# 1P3W_v1p3.net
KiCad netlist of a schematic drawn in EAGLE
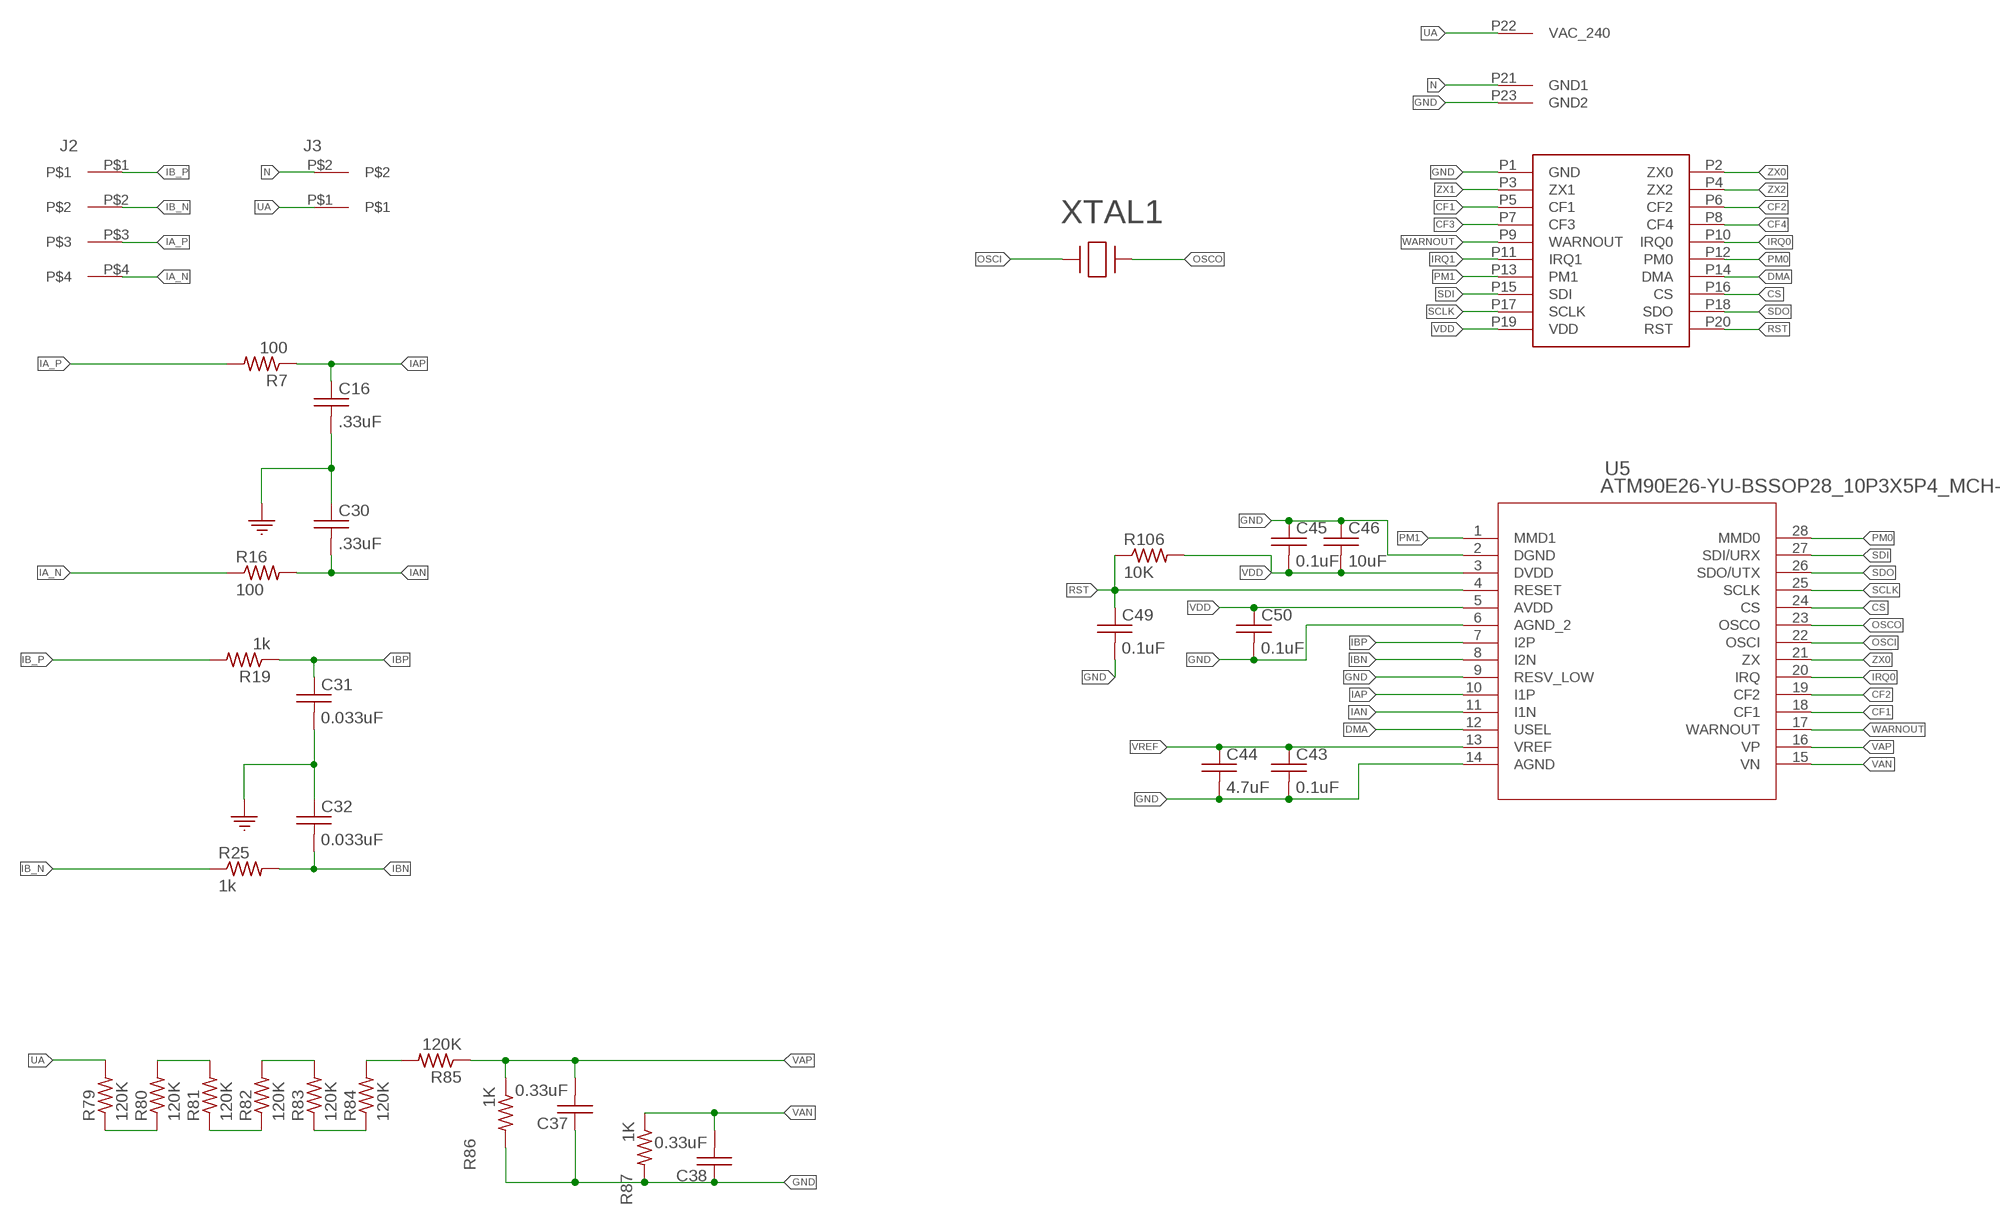
[diagram p0: schematic, sheet 1]

(export (version "E")
  (design (tool "Eeschema 10.0.6"))
  (components
    (comp (ref "C16")
      (value ".33uF")
      (footprint "eagle-import:0402")
      (libsource (lib "eagle-import") (part "C_0402"))
    )
    (comp (ref "C30")
      (value ".33uF")
      (footprint "eagle-import:0402")
      (libsource (lib "eagle-import") (part "C_0402"))
    )
    (comp (ref "C31")
      (value "0.033uF")
      (footprint "eagle-import:0402")
      (libsource (lib "eagle-import") (part "C_0402"))
    )
    (comp (ref "C32")
      (value "0.033uF")
      (footprint "eagle-import:0402")
      (libsource (lib "eagle-import") (part "C_0402"))
    )
    (comp (ref "C37")
      (value "0.33uF")
      (footprint "eagle-import:0402")
      (libsource (lib "eagle-import") (part "C_0402"))
    )
    (comp (ref "C38")
      (value "0.33uF")
      (footprint "eagle-import:0402")
      (libsource (lib "eagle-import") (part "C_0402"))
    )
    (comp (ref "C43")
      (value "0.1uF")
      (footprint "eagle-import:0402")
      (libsource (lib "eagle-import") (part "C_0402"))
    )
    (comp (ref "C44")
      (value "4.7uF")
      (footprint "eagle-import:0402")
      (libsource (lib "eagle-import") (part "C_0402"))
    )
    (comp (ref "C45")
      (value "0.1uF")
      (footprint "eagle-import:0402")
      (libsource (lib "eagle-import") (part "C_0402"))
    )
    (comp (ref "C46")
      (value "10uF")
      (footprint "eagle-import:0402")
      (libsource (lib "eagle-import") (part "C_0402"))
    )
    (comp (ref "C49")
      (value "0.1uF")
      (footprint "eagle-import:0402")
      (libsource (lib "eagle-import") (part "C_0402"))
    )
    (comp (ref "C50")
      (value "0.1uF")
      (footprint "eagle-import:0402")
      (libsource (lib "eagle-import") (part "C_0402"))
    )
    (comp (ref "J2")
      (value "3.81MM_1_X_4_RT_ANGLE_PLUG_HEADER")
      (footprint "eagle-import:1X4_3.81MM_PITCH")
      (libsource (lib "eagle-import") (part "3.81MM_1_X_4_RT_ANGLE_PLUG_HEADER"))
    )
    (comp (ref "J3")
      (value "3.81MM_1_X_2_RT_ANGLE_PLUG_HEADER")
      (footprint "eagle-import:2_3.81MM_PITCH")
      (libsource (lib "eagle-import") (part "3.81MM_1_X_2_RT_ANGLE_PLUG_HEADER"))
    )
    (comp (ref "R7")
      (value "100")
      (footprint "eagle-import:0402")
      (libsource (lib "eagle-import") (part "R_0402"))
    )
    (comp (ref "R16")
      (value "100")
      (footprint "eagle-import:0402")
      (libsource (lib "eagle-import") (part "R_0402"))
    )
    (comp (ref "R19")
      (value "1k")
      (footprint "eagle-import:0402")
      (libsource (lib "eagle-import") (part "R_0402"))
    )
    (comp (ref "R25")
      (value "1k")
      (footprint "eagle-import:0402")
      (libsource (lib "eagle-import") (part "R_0402"))
    )
    (comp (ref "R79")
      (value "120K")
      (footprint "eagle-import:0402")
      (libsource (lib "eagle-import") (part "R_0402"))
    )
    (comp (ref "R80")
      (value "120K")
      (footprint "eagle-import:0402")
      (libsource (lib "eagle-import") (part "R_0402"))
    )
    (comp (ref "R81")
      (value "120K")
      (footprint "eagle-import:0402")
      (libsource (lib "eagle-import") (part "R_0402"))
    )
    (comp (ref "R82")
      (value "120K")
      (footprint "eagle-import:0402")
      (libsource (lib "eagle-import") (part "R_0402"))
    )
    (comp (ref "R83")
      (value "120K")
      (footprint "eagle-import:0402")
      (libsource (lib "eagle-import") (part "R_0402"))
    )
    (comp (ref "R84")
      (value "120K")
      (footprint "eagle-import:0402")
      (libsource (lib "eagle-import") (part "R_0402"))
    )
    (comp (ref "R85")
      (value "120K")
      (footprint "eagle-import:0402")
      (libsource (lib "eagle-import") (part "R_0402"))
    )
    (comp (ref "R86")
      (value "1K")
      (footprint "eagle-import:0402")
      (libsource (lib "eagle-import") (part "R_0402"))
    )
    (comp (ref "R87")
      (value "1K")
      (footprint "eagle-import:0402")
      (libsource (lib "eagle-import") (part "R_0402"))
    )
    (comp (ref "R106")
      (value "10K")
      (footprint "eagle-import:0402")
      (libsource (lib "eagle-import") (part "R_0402"))
    )
    (comp (ref "U$1")
      (value "METER_BASE")
      (footprint "eagle-import:METER_BASE")
      (libsource (lib "eagle-import") (part "METER_BASE"))
    )
    (comp (ref "U5")
      (value "ATM90E26-YU-BSSOP28_10P3X5P4_MCH-M")
      (footprint "eagle-import:SSOP28_10P3X5P4_MCH-M")
      (fields
        (field (name "MANUFACTURER_PART_NUMBER") "ATM90E26-YU-B")
        (field (name "COPYRIGHT") "Copyright (C) 2018 Accelerated Designs. All rights reserved")
      )
      (libsource (lib "eagle-import") (part "ATM90E26-YU-BSSOP28_10P3X5P4_MCH-M"))
    )
    (comp (ref "XTAL1")
      (value "ABLS-8.192MHZ-B2-TXTAL_HC/49US_ABLS_ABR-M")
      (footprint "eagle-import:XTAL_HC_49US_ABLS_ABR-M")
      (fields
        (field (name "MANUFACTURER_PART_NUMBER") "ABLS-8.192MHZ-B2-T")
        (field (name "COPYRIGHT") "Copyright (C) 2018 Accelerated Designs. All rights reserved")
      )
      (libsource (lib "eagle-import") (part "ABLS-8.192MHZ-B2-TXTAL_HC/49US_ABLS_ABR-M"))
    )
  )
  (nets
    (net (code "1") (name "CF1") (class "Default")
      (node (ref "U$1") (pin "P5") (pinfunction "CF1_P5") (pintype "bidirectional"))
      (node (ref "U5") (pin "18") (pinfunction "CF1_18") (pintype "bidirectional"))
    )
    (net (code "2") (name "CF2") (class "Default")
      (node (ref "U$1") (pin "P6") (pinfunction "CF2_P6") (pintype "bidirectional"))
      (node (ref "U5") (pin "19") (pinfunction "CF2_19") (pintype "bidirectional"))
    )
    (net (code "3") (name "CF3") (class "Default")
      (node (ref "U$1") (pin "P7") (pinfunction "CF3_P7") (pintype "bidirectional"))
    )
    (net (code "4") (name "CF4") (class "Default")
      (node (ref "U$1") (pin "P8") (pinfunction "CF4_P8") (pintype "bidirectional"))
    )
    (net (code "5") (name "CS") (class "Default")
      (node (ref "U$1") (pin "P16") (pinfunction "CS_P16") (pintype "bidirectional"))
      (node (ref "U5") (pin "24") (pinfunction "CS_24") (pintype "passive"))
    )
    (net (code "6") (name "DMA") (class "Default")
      (node (ref "U$1") (pin "P14") (pinfunction "DMA_P14") (pintype "bidirectional"))
      (node (ref "U5") (pin "12") (pinfunction "USEL_12") (pintype "passive"))
    )
    (net (code "7") (name "GND") (class "Default")
      (node (ref "C16") (pin "P$2") (pinfunction "2_P$2") (pintype "passive"))
      (node (ref "C30") (pin "P$1") (pinfunction "1_P$1") (pintype "passive"))
      (node (ref "C31") (pin "P$2") (pinfunction "2_P$2") (pintype "passive"))
      (node (ref "C32") (pin "P$1") (pinfunction "1_P$1") (pintype "passive"))
      (node (ref "C37") (pin "P$1") (pinfunction "1_P$1") (pintype "passive"))
      (node (ref "C38") (pin "P$1") (pinfunction "1_P$1") (pintype "passive"))
      (node (ref "C43") (pin "P$2") (pinfunction "2_P$2") (pintype "passive"))
      (node (ref "C44") (pin "P$2") (pinfunction "2_P$2") (pintype "passive"))
      (node (ref "C45") (pin "P$1") (pinfunction "1_P$1") (pintype "passive"))
      (node (ref "C46") (pin "P$1") (pinfunction "1_P$1") (pintype "passive"))
      (node (ref "C49") (pin "P$2") (pinfunction "2_P$2") (pintype "passive"))
      (node (ref "C50") (pin "P$2") (pinfunction "2_P$2") (pintype "passive"))
      (node (ref "R86") (pin "P$2") (pinfunction "2_P$2") (pintype "passive"))
      (node (ref "R87") (pin "P$2") (pinfunction "2_P$2") (pintype "passive"))
      (node (ref "U$1") (pin "P1") (pinfunction "GND_P1") (pintype "bidirectional"))
      (node (ref "U$1") (pin "P23") (pinfunction "GND2_P23") (pintype "bidirectional"))
      (node (ref "U5") (pin "14") (pinfunction "AGND_14") (pintype "passive"))
      (node (ref "U5") (pin "2") (pinfunction "DGND_2") (pintype "passive"))
      (node (ref "U5") (pin "6") (pinfunction "AGND_2_6") (pintype "passive"))
      (node (ref "U5") (pin "9") (pinfunction "RESV_LOW_9") (pintype "passive"))
    )
    (net (code "8") (name "IAN") (class "Default")
      (node (ref "C30") (pin "P$2") (pinfunction "2_P$2") (pintype "passive"))
      (node (ref "R16") (pin "P$2") (pinfunction "2_P$2") (pintype "passive"))
      (node (ref "U5") (pin "11") (pinfunction "I1N_11") (pintype "bidirectional"))
    )
    (net (code "9") (name "IAP") (class "Default")
      (node (ref "C16") (pin "P$1") (pinfunction "1_P$1") (pintype "passive"))
      (node (ref "R7") (pin "P$1") (pinfunction "1_P$1") (pintype "passive"))
      (node (ref "U5") (pin "10") (pinfunction "I1P_10") (pintype "bidirectional"))
    )
    (net (code "10") (name "IA_N") (class "Default")
      (node (ref "J2") (pin "P$4") (pinfunction "P$4_P$4") (pintype "bidirectional"))
      (node (ref "R16") (pin "P$1") (pinfunction "1_P$1") (pintype "passive"))
    )
    (net (code "11") (name "IA_P") (class "Default")
      (node (ref "J2") (pin "P$3") (pinfunction "P$3_P$3") (pintype "bidirectional"))
      (node (ref "R7") (pin "P$2") (pinfunction "2_P$2") (pintype "passive"))
    )
    (net (code "12") (name "IBN") (class "Default")
      (node (ref "C32") (pin "P$2") (pinfunction "2_P$2") (pintype "passive"))
      (node (ref "R25") (pin "P$2") (pinfunction "2_P$2") (pintype "passive"))
      (node (ref "U5") (pin "8") (pinfunction "I2N_8") (pintype "bidirectional"))
    )
    (net (code "13") (name "IBP") (class "Default")
      (node (ref "C31") (pin "P$1") (pinfunction "1_P$1") (pintype "passive"))
      (node (ref "R19") (pin "P$1") (pinfunction "1_P$1") (pintype "passive"))
      (node (ref "U5") (pin "7") (pinfunction "I2P_7") (pintype "bidirectional"))
    )
    (net (code "14") (name "IB_N") (class "Default")
      (node (ref "J2") (pin "P$2") (pinfunction "P$2_P$2") (pintype "bidirectional"))
      (node (ref "R25") (pin "P$1") (pinfunction "1_P$1") (pintype "passive"))
    )
    (net (code "15") (name "IB_P") (class "Default")
      (node (ref "J2") (pin "P$1") (pinfunction "P$1_P$1") (pintype "bidirectional"))
      (node (ref "R19") (pin "P$2") (pinfunction "2_P$2") (pintype "passive"))
    )
    (net (code "16") (name "IRQ0") (class "Default")
      (node (ref "U$1") (pin "P10") (pinfunction "IRQ0_P10") (pintype "bidirectional"))
      (node (ref "U5") (pin "20") (pinfunction "IRQ_20") (pintype "passive"))
    )
    (net (code "17") (name "IRQ1") (class "Default")
      (node (ref "U$1") (pin "P11") (pinfunction "IRQ1_P11") (pintype "bidirectional"))
    )
    (net (code "18") (name "N") (class "Default")
      (node (ref "J3") (pin "P$2") (pinfunction "P$2_P$2") (pintype "bidirectional"))
      (node (ref "U$1") (pin "P21") (pinfunction "GND1_P21") (pintype "bidirectional"))
    )
    (net (code "19") (name "Net-(R79-1)") (class "Default")
      (node (ref "R79") (pin "P$1") (pinfunction "1_P$1") (pintype "passive"))
      (node (ref "R80") (pin "P$1") (pinfunction "1_P$1") (pintype "passive"))
    )
    (net (code "20") (name "Net-(R80-2)") (class "Default")
      (node (ref "R80") (pin "P$2") (pinfunction "2_P$2") (pintype "passive"))
      (node (ref "R81") (pin "P$2") (pinfunction "2_P$2") (pintype "passive"))
    )
    (net (code "21") (name "Net-(R81-1)") (class "Default")
      (node (ref "R81") (pin "P$1") (pinfunction "1_P$1") (pintype "passive"))
      (node (ref "R82") (pin "P$1") (pinfunction "1_P$1") (pintype "passive"))
    )
    (net (code "22") (name "Net-(R82-2)") (class "Default")
      (node (ref "R82") (pin "P$2") (pinfunction "2_P$2") (pintype "passive"))
      (node (ref "R83") (pin "P$2") (pinfunction "2_P$2") (pintype "passive"))
    )
    (net (code "23") (name "Net-(R83-1)") (class "Default")
      (node (ref "R83") (pin "P$1") (pinfunction "1_P$1") (pintype "passive"))
      (node (ref "R84") (pin "P$1") (pinfunction "1_P$1") (pintype "passive"))
    )
    (net (code "24") (name "Net-(R84-2)") (class "Default")
      (node (ref "R84") (pin "P$2") (pinfunction "2_P$2") (pintype "passive"))
      (node (ref "R85") (pin "P$2") (pinfunction "2_P$2") (pintype "passive"))
    )
    (net (code "25") (name "OSCI") (class "Default")
      (node (ref "U5") (pin "22") (pinfunction "OSCI_22") (pintype "passive"))
      (node (ref "XTAL1") (pin "1") (pinfunction "1_1") (pintype "passive"))
    )
    (net (code "26") (name "OSCO") (class "Default")
      (node (ref "U5") (pin "23") (pinfunction "OSCO_23") (pintype "passive"))
      (node (ref "XTAL1") (pin "2") (pinfunction "2_2") (pintype "passive"))
    )
    (net (code "27") (name "PM0") (class "Default")
      (node (ref "U$1") (pin "P12") (pinfunction "PM0_P12") (pintype "bidirectional"))
      (node (ref "U5") (pin "28") (pinfunction "MMD0_28") (pintype "bidirectional"))
    )
    (net (code "28") (name "PM1") (class "Default")
      (node (ref "U$1") (pin "P13") (pinfunction "PM1_P13") (pintype "bidirectional"))
      (node (ref "U5") (pin "1") (pinfunction "MMD1_1") (pintype "bidirectional"))
    )
    (net (code "29") (name "RST") (class "Default")
      (node (ref "C49") (pin "P$1") (pinfunction "1_P$1") (pintype "passive"))
      (node (ref "R106") (pin "P$1") (pinfunction "1_P$1") (pintype "passive"))
      (node (ref "U$1") (pin "P20") (pinfunction "RST_P20") (pintype "bidirectional"))
      (node (ref "U5") (pin "4") (pinfunction "RESET_4") (pintype "passive"))
    )
    (net (code "30") (name "SCLK") (class "Default")
      (node (ref "U$1") (pin "P17") (pinfunction "SCLK_P17") (pintype "bidirectional"))
      (node (ref "U5") (pin "25") (pinfunction "SCLK_25") (pintype "passive"))
    )
    (net (code "31") (name "SDI") (class "Default")
      (node (ref "U$1") (pin "P15") (pinfunction "SDI_P15") (pintype "bidirectional"))
      (node (ref "U5") (pin "27") (pinfunction "SDI/URX_27") (pintype "passive"))
    )
    (net (code "32") (name "SDO") (class "Default")
      (node (ref "U$1") (pin "P18") (pinfunction "SDO_P18") (pintype "bidirectional"))
      (node (ref "U5") (pin "26") (pinfunction "SDO/UTX_26") (pintype "passive"))
    )
    (net (code "33") (name "UA") (class "Default")
      (node (ref "J3") (pin "P$1") (pinfunction "P$1_P$1") (pintype "bidirectional"))
      (node (ref "R79") (pin "P$2") (pinfunction "2_P$2") (pintype "passive"))
      (node (ref "U$1") (pin "P22") (pinfunction "VAC_240_P22") (pintype "bidirectional"))
    )
    (net (code "34") (name "VAN") (class "Default")
      (node (ref "C38") (pin "P$2") (pinfunction "2_P$2") (pintype "passive"))
      (node (ref "R87") (pin "P$1") (pinfunction "1_P$1") (pintype "passive"))
      (node (ref "U5") (pin "15") (pinfunction "VN_15") (pintype "passive"))
    )
    (net (code "35") (name "VAP") (class "Default")
      (node (ref "C37") (pin "P$2") (pinfunction "2_P$2") (pintype "passive"))
      (node (ref "R85") (pin "P$1") (pinfunction "1_P$1") (pintype "passive"))
      (node (ref "R86") (pin "P$1") (pinfunction "1_P$1") (pintype "passive"))
      (node (ref "U5") (pin "16") (pinfunction "VP_16") (pintype "passive"))
    )
    (net (code "36") (name "VDD") (class "Default")
      (node (ref "C45") (pin "P$2") (pinfunction "2_P$2") (pintype "passive"))
      (node (ref "C46") (pin "P$2") (pinfunction "2_P$2") (pintype "passive"))
      (node (ref "C50") (pin "P$1") (pinfunction "1_P$1") (pintype "passive"))
      (node (ref "R106") (pin "P$2") (pinfunction "2_P$2") (pintype "passive"))
      (node (ref "U$1") (pin "P19") (pinfunction "VDD_P19") (pintype "bidirectional"))
      (node (ref "U5") (pin "3") (pinfunction "DVDD_3") (pintype "power_in"))
      (node (ref "U5") (pin "5") (pinfunction "AVDD_5") (pintype "power_in"))
    )
    (net (code "37") (name "VREF") (class "Default")
      (node (ref "C43") (pin "P$1") (pinfunction "1_P$1") (pintype "passive"))
      (node (ref "C44") (pin "P$1") (pinfunction "1_P$1") (pintype "passive"))
      (node (ref "U5") (pin "13") (pinfunction "VREF_13") (pintype "power_in"))
    )
    (net (code "38") (name "WARNOUT") (class "Default")
      (node (ref "U$1") (pin "P9") (pinfunction "WARNOUT_P9") (pintype "bidirectional"))
      (node (ref "U5") (pin "17") (pinfunction "WARNOUT_17") (pintype "output"))
    )
    (net (code "39") (name "ZX0") (class "Default")
      (node (ref "U$1") (pin "P2") (pinfunction "ZX0_P2") (pintype "bidirectional"))
      (node (ref "U5") (pin "21") (pinfunction "ZX_21") (pintype "passive"))
    )
    (net (code "40") (name "ZX1") (class "Default")
      (node (ref "U$1") (pin "P3") (pinfunction "ZX1_P3") (pintype "bidirectional"))
    )
    (net (code "41") (name "ZX2") (class "Default")
      (node (ref "U$1") (pin "P4") (pinfunction "ZX2_P4") (pintype "bidirectional"))
    )
  )
)
